# 4_waffling60-SE_periferals.net
KiCad netlist of a schematic drawn in Altium Designer
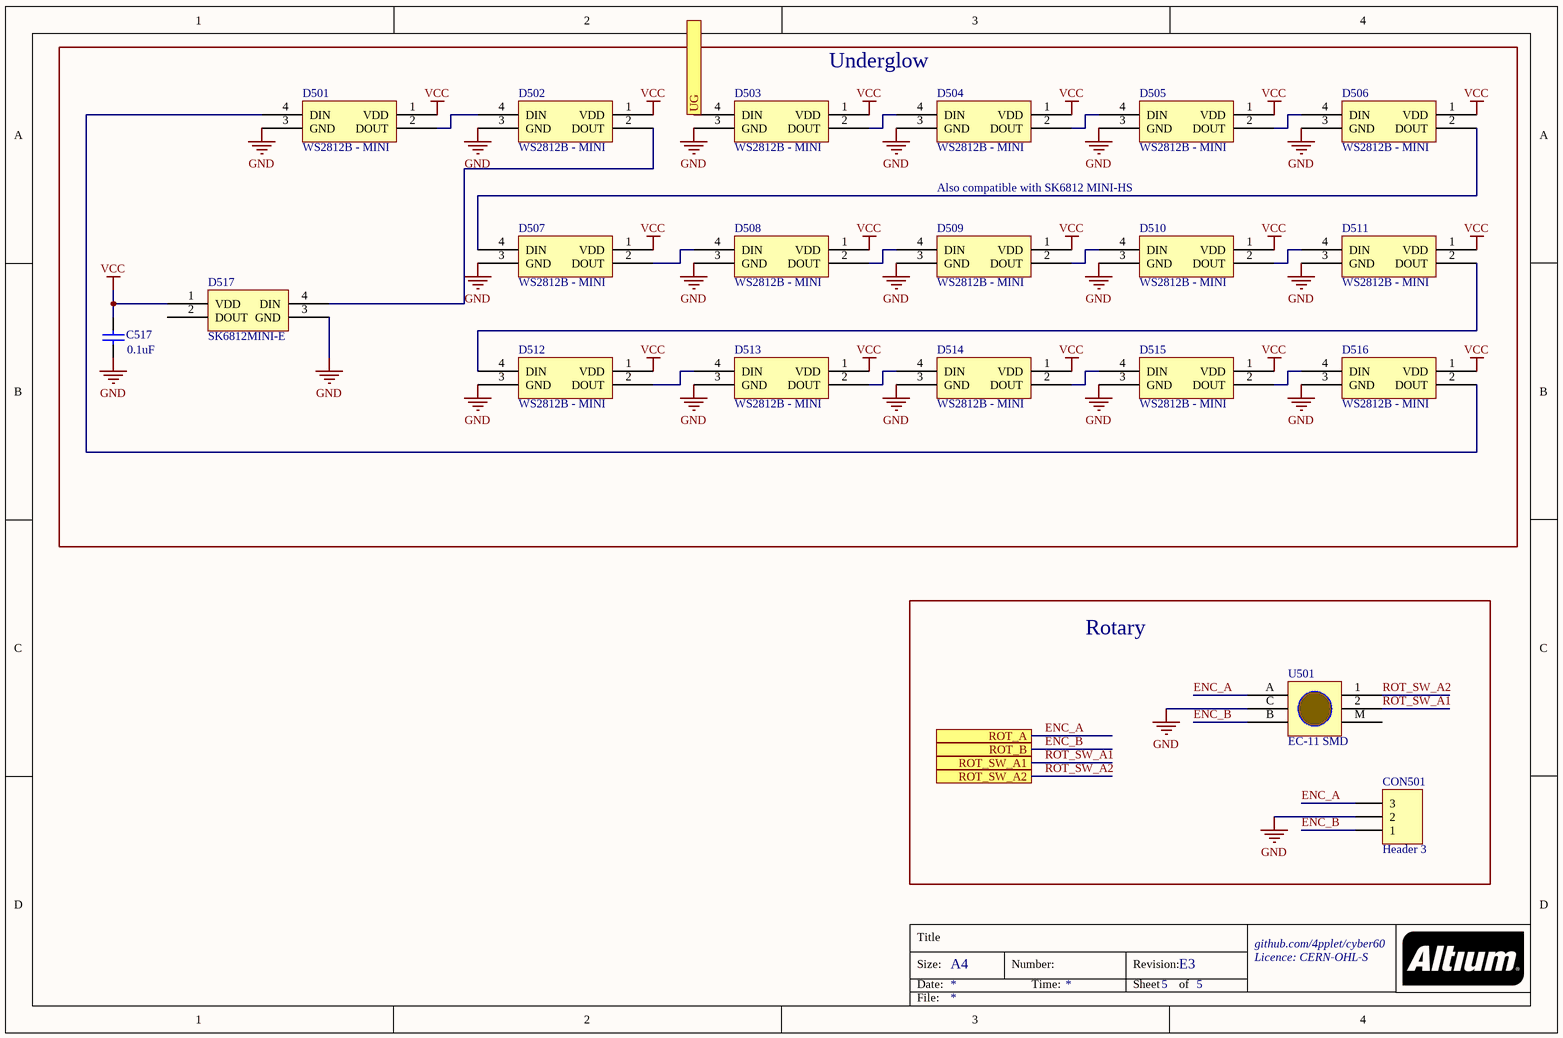
[diagram p0: 4_waffling60-SE_periferals.SchDoc]

(export (version "E")
  (design (tool "Eeschema 10.0.6"))
  (components
    (comp (ref "C517")
      (value "0.1uF")
      (footprint "C0603[1608]")
      (description "Capacitor")
      (fields (field (name "LCSC PART #") "C14663") (field (name "MRF.PART") "CC0603KRX7R9BB104"))
      (libsource (lib "Miscellaneous Devices") (part "Cap"))
    )
    (comp (ref "CON501")
      (value "Header 3")
      (footprint "HDR1X3")
      (description "Header, 3-Pin")
      (libsource (lib "Miscellaneous Connectors") (part "Header 3"))
    )
    (comp (ref "D501")
      (value "WS2812B - MINI")
      (footprint "WS2812B - 2020")
      (fields (field (name "LCSC PART #") "C965555") (field (name "MRF.PART") "WS2812B-2020"))
      (libsource (lib "Keebs") (part "WS2812B"))
    )
    (comp (ref "D502")
      (value "WS2812B - MINI")
      (footprint "WS2812B - 2020")
      (fields (field (name "LCSC PART #") "C965555") (field (name "MRF.PART") "WS2812B-2020"))
      (libsource (lib "Keebs") (part "WS2812B"))
    )
    (comp (ref "D503")
      (value "WS2812B - MINI")
      (footprint "WS2812B - 2020")
      (fields (field (name "LCSC PART #") "C965555") (field (name "MRF.PART") "WS2812B-2020"))
      (libsource (lib "Keebs") (part "WS2812B"))
    )
    (comp (ref "D504")
      (value "WS2812B - MINI")
      (footprint "WS2812B - 2020")
      (fields (field (name "LCSC PART #") "C965555") (field (name "MRF.PART") "WS2812B-2020"))
      (libsource (lib "Keebs") (part "WS2812B"))
    )
    (comp (ref "D505")
      (value "WS2812B - MINI")
      (footprint "WS2812B - 2020")
      (fields (field (name "LCSC PART #") "C965555") (field (name "MRF.PART") "WS2812B-2020"))
      (libsource (lib "Keebs") (part "WS2812B"))
    )
    (comp (ref "D506")
      (value "WS2812B - MINI")
      (footprint "WS2812B - 2020")
      (fields (field (name "LCSC PART #") "C965555") (field (name "MRF.PART") "WS2812B-2020"))
      (libsource (lib "Keebs") (part "WS2812B"))
    )
    (comp (ref "D507")
      (value "WS2812B - MINI")
      (footprint "WS2812B - 2020")
      (fields (field (name "LCSC PART #") "C965555") (field (name "MRF.PART") "WS2812B-2020"))
      (libsource (lib "Keebs") (part "WS2812B"))
    )
    (comp (ref "D508")
      (value "WS2812B - MINI")
      (footprint "WS2812B - 2020")
      (fields (field (name "LCSC PART #") "C965555") (field (name "MRF.PART") "WS2812B-2020"))
      (libsource (lib "Keebs") (part "WS2812B"))
    )
    (comp (ref "D509")
      (value "WS2812B - MINI")
      (footprint "WS2812B - 2020")
      (fields (field (name "LCSC PART #") "C965555") (field (name "MRF.PART") "WS2812B-2020"))
      (libsource (lib "Keebs") (part "WS2812B"))
    )
    (comp (ref "D510")
      (value "WS2812B - MINI")
      (footprint "WS2812B - 2020")
      (fields (field (name "LCSC PART #") "C965555") (field (name "MRF.PART") "WS2812B-2020"))
      (libsource (lib "Keebs") (part "WS2812B"))
    )
    (comp (ref "D511")
      (value "WS2812B - MINI")
      (footprint "WS2812B - 2020")
      (fields (field (name "LCSC PART #") "C965555") (field (name "MRF.PART") "WS2812B-2020"))
      (libsource (lib "Keebs") (part "WS2812B"))
    )
    (comp (ref "D512")
      (value "WS2812B - MINI")
      (footprint "WS2812B - 2020")
      (fields (field (name "LCSC PART #") "C965555") (field (name "MRF.PART") "WS2812B-2020"))
      (libsource (lib "Keebs") (part "WS2812B"))
    )
    (comp (ref "D513")
      (value "WS2812B - MINI")
      (footprint "WS2812B - 2020")
      (fields (field (name "LCSC PART #") "C965555") (field (name "MRF.PART") "WS2812B-2020"))
      (libsource (lib "Keebs") (part "WS2812B"))
    )
    (comp (ref "D514")
      (value "WS2812B - MINI")
      (footprint "WS2812B - 2020")
      (fields (field (name "LCSC PART #") "C965555") (field (name "MRF.PART") "WS2812B-2020"))
      (libsource (lib "Keebs") (part "WS2812B"))
    )
    (comp (ref "D515")
      (value "WS2812B - MINI")
      (footprint "WS2812B - 2020")
      (fields (field (name "LCSC PART #") "C965555") (field (name "MRF.PART") "WS2812B-2020"))
      (libsource (lib "Keebs") (part "WS2812B"))
    )
    (comp (ref "D516")
      (value "WS2812B - MINI")
      (footprint "WS2812B - 2020")
      (fields (field (name "LCSC PART #") "C965555") (field (name "MRF.PART") "WS2812B-2020"))
      (libsource (lib "Keebs") (part "WS2812B"))
    )
    (comp (ref "D517")
      (value "SK6812MINI-E")
      (footprint "SK6812MINI-E - shaped")
      (fields (field (name "LCSC PART #") "C524051") (field (name "MRF.PART") "DY-S352818/RGBC/6812-2T"))
      (libsource (lib "Keebs") (part "SK6812MINI-E"))
    )
    (comp (ref "U501") (value "EC-11 SMD") (footprint "EC11-SMD") (libsource (lib "Keebs") (part "EC-11")))
  )
  (nets
    (net (code "1") (name "/ENC_A") (class "Default")
      (node (ref "CON501") (pin "3") (pinfunction "3_3") (pintype "passive"))
      (node (ref "U501") (pin "A") (pinfunction "B_A") (pintype "passive"))
    )
    (net (code "2") (name "/ENC_B") (class "Default")
      (node (ref "CON501") (pin "1") (pinfunction "1_1") (pintype "passive"))
      (node (ref "U501") (pin "B") (pinfunction "B_B") (pintype "passive"))
    )
    (net (code "3") (name "/ROT_SW_A1") (class "Default")
      (node (ref "U501") (pin "2") (pinfunction "2_2") (pintype "passive"))
    )
    (net (code "4") (name "/ROT_SW_A2") (class "Default")
      (node (ref "U501") (pin "1") (pinfunction "1_1") (pintype "passive"))
    )
    (net (code "5") (name "/UG") (class "Default")
      (node (ref "D503") (pin "4") (pinfunction "DIN_4") (pintype "passive"))
    )
    (net (code "6") (name "GND") (class "Default")
      (node (ref "C517") (pin "1") (pinfunction "1_1") (pintype "passive"))
      (node (ref "CON501") (pin "2") (pinfunction "2_2") (pintype "passive"))
      (node (ref "D501") (pin "3") (pinfunction "GND_3") (pintype "passive"))
      (node (ref "D502") (pin "3") (pinfunction "GND_3") (pintype "passive"))
      (node (ref "D503") (pin "3") (pinfunction "GND_3") (pintype "passive"))
      (node (ref "D504") (pin "3") (pinfunction "GND_3") (pintype "passive"))
      (node (ref "D505") (pin "3") (pinfunction "GND_3") (pintype "passive"))
      (node (ref "D506") (pin "3") (pinfunction "GND_3") (pintype "passive"))
      (node (ref "D507") (pin "3") (pinfunction "GND_3") (pintype "passive"))
      (node (ref "D508") (pin "3") (pinfunction "GND_3") (pintype "passive"))
      (node (ref "D509") (pin "3") (pinfunction "GND_3") (pintype "passive"))
      (node (ref "D510") (pin "3") (pinfunction "GND_3") (pintype "passive"))
      (node (ref "D511") (pin "3") (pinfunction "GND_3") (pintype "passive"))
      (node (ref "D512") (pin "3") (pinfunction "GND_3") (pintype "passive"))
      (node (ref "D513") (pin "3") (pinfunction "GND_3") (pintype "passive"))
      (node (ref "D514") (pin "3") (pinfunction "GND_3") (pintype "passive"))
      (node (ref "D515") (pin "3") (pinfunction "GND_3") (pintype "passive"))
      (node (ref "D516") (pin "3") (pinfunction "GND_3") (pintype "passive"))
      (node (ref "D517") (pin "3") (pinfunction "GND_3") (pintype "passive"))
      (node (ref "U501") (pin "C") (pinfunction "C_C") (pintype "passive"))
    )
    (net (code "7") (name "Net-(D501-DIN)") (class "Default")
      (node (ref "D501") (pin "4") (pinfunction "DIN_4") (pintype "passive"))
      (node (ref "D516") (pin "2") (pinfunction "DOUT_2") (pintype "passive"))
    )
    (net (code "8") (name "Net-(D501-DOUT)") (class "Default")
      (node (ref "D501") (pin "2") (pinfunction "DOUT_2") (pintype "passive"))
      (node (ref "D502") (pin "4") (pinfunction "DIN_4") (pintype "passive"))
    )
    (net (code "9") (name "Net-(D502-DOUT)") (class "Default")
      (node (ref "D502") (pin "2") (pinfunction "DOUT_2") (pintype "passive"))
      (node (ref "D517") (pin "4") (pinfunction "DIN_4") (pintype "passive"))
    )
    (net (code "10") (name "Net-(D503-DOUT)") (class "Default")
      (node (ref "D503") (pin "2") (pinfunction "DOUT_2") (pintype "passive"))
      (node (ref "D504") (pin "4") (pinfunction "DIN_4") (pintype "passive"))
    )
    (net (code "11") (name "Net-(D504-DOUT)") (class "Default")
      (node (ref "D504") (pin "2") (pinfunction "DOUT_2") (pintype "passive"))
      (node (ref "D505") (pin "4") (pinfunction "DIN_4") (pintype "passive"))
    )
    (net (code "12") (name "Net-(D505-DOUT)") (class "Default")
      (node (ref "D505") (pin "2") (pinfunction "DOUT_2") (pintype "passive"))
      (node (ref "D506") (pin "4") (pinfunction "DIN_4") (pintype "passive"))
    )
    (net (code "13") (name "Net-(D506-DOUT)") (class "Default")
      (node (ref "D506") (pin "2") (pinfunction "DOUT_2") (pintype "passive"))
      (node (ref "D507") (pin "4") (pinfunction "DIN_4") (pintype "passive"))
    )
    (net (code "14") (name "Net-(D507-DOUT)") (class "Default")
      (node (ref "D507") (pin "2") (pinfunction "DOUT_2") (pintype "passive"))
      (node (ref "D508") (pin "4") (pinfunction "DIN_4") (pintype "passive"))
    )
    (net (code "15") (name "Net-(D508-DOUT)") (class "Default")
      (node (ref "D508") (pin "2") (pinfunction "DOUT_2") (pintype "passive"))
      (node (ref "D509") (pin "4") (pinfunction "DIN_4") (pintype "passive"))
    )
    (net (code "16") (name "Net-(D509-DOUT)") (class "Default")
      (node (ref "D509") (pin "2") (pinfunction "DOUT_2") (pintype "passive"))
      (node (ref "D510") (pin "4") (pinfunction "DIN_4") (pintype "passive"))
    )
    (net (code "17") (name "Net-(D510-DOUT)") (class "Default")
      (node (ref "D510") (pin "2") (pinfunction "DOUT_2") (pintype "passive"))
      (node (ref "D511") (pin "4") (pinfunction "DIN_4") (pintype "passive"))
    )
    (net (code "18") (name "Net-(D511-DOUT)") (class "Default")
      (node (ref "D511") (pin "2") (pinfunction "DOUT_2") (pintype "passive"))
      (node (ref "D512") (pin "4") (pinfunction "DIN_4") (pintype "passive"))
    )
    (net (code "19") (name "Net-(D512-DOUT)") (class "Default")
      (node (ref "D512") (pin "2") (pinfunction "DOUT_2") (pintype "passive"))
      (node (ref "D513") (pin "4") (pinfunction "DIN_4") (pintype "passive"))
    )
    (net (code "20") (name "Net-(D513-DOUT)") (class "Default")
      (node (ref "D513") (pin "2") (pinfunction "DOUT_2") (pintype "passive"))
      (node (ref "D514") (pin "4") (pinfunction "DIN_4") (pintype "passive"))
    )
    (net (code "21") (name "Net-(D514-DOUT)") (class "Default")
      (node (ref "D514") (pin "2") (pinfunction "DOUT_2") (pintype "passive"))
      (node (ref "D515") (pin "4") (pinfunction "DIN_4") (pintype "passive"))
    )
    (net (code "22") (name "Net-(D515-DOUT)") (class "Default")
      (node (ref "D515") (pin "2") (pinfunction "DOUT_2") (pintype "passive"))
      (node (ref "D516") (pin "4") (pinfunction "DIN_4") (pintype "passive"))
    )
    (net (code "23") (name "VCC") (class "Default")
      (node (ref "C517") (pin "2") (pinfunction "2_2") (pintype "passive"))
      (node (ref "D501") (pin "1") (pinfunction "VDD_1") (pintype "passive"))
      (node (ref "D502") (pin "1") (pinfunction "VDD_1") (pintype "passive"))
      (node (ref "D503") (pin "1") (pinfunction "VDD_1") (pintype "passive"))
      (node (ref "D504") (pin "1") (pinfunction "VDD_1") (pintype "passive"))
      (node (ref "D505") (pin "1") (pinfunction "VDD_1") (pintype "passive"))
      (node (ref "D506") (pin "1") (pinfunction "VDD_1") (pintype "passive"))
      (node (ref "D507") (pin "1") (pinfunction "VDD_1") (pintype "passive"))
      (node (ref "D508") (pin "1") (pinfunction "VDD_1") (pintype "passive"))
      (node (ref "D509") (pin "1") (pinfunction "VDD_1") (pintype "passive"))
      (node (ref "D510") (pin "1") (pinfunction "VDD_1") (pintype "passive"))
      (node (ref "D511") (pin "1") (pinfunction "VDD_1") (pintype "passive"))
      (node (ref "D512") (pin "1") (pinfunction "VDD_1") (pintype "passive"))
      (node (ref "D513") (pin "1") (pinfunction "VDD_1") (pintype "passive"))
      (node (ref "D514") (pin "1") (pinfunction "VDD_1") (pintype "passive"))
      (node (ref "D515") (pin "1") (pinfunction "VDD_1") (pintype "passive"))
      (node (ref "D516") (pin "1") (pinfunction "VDD_1") (pintype "passive"))
      (node (ref "D517") (pin "1") (pinfunction "VDD_1") (pintype "passive"))
    )
    (net (code "24") (name "unconnected-(D517-DOUT-Pad2)") (class "Default")
      (node (ref "D517") (pin "2") (pinfunction "DOUT_2") (pintype "passive"))
    )
    (net (code "25") (name "unconnected-(U501-PadM)") (class "Default")
      (node (ref "U501") (pin "M") (pinfunction "M_M") (pintype "passive"))
    )
  )
)
